# UnsungHeroes.net
KiCad netlist of a schematic drawn in EasyEDA Pro
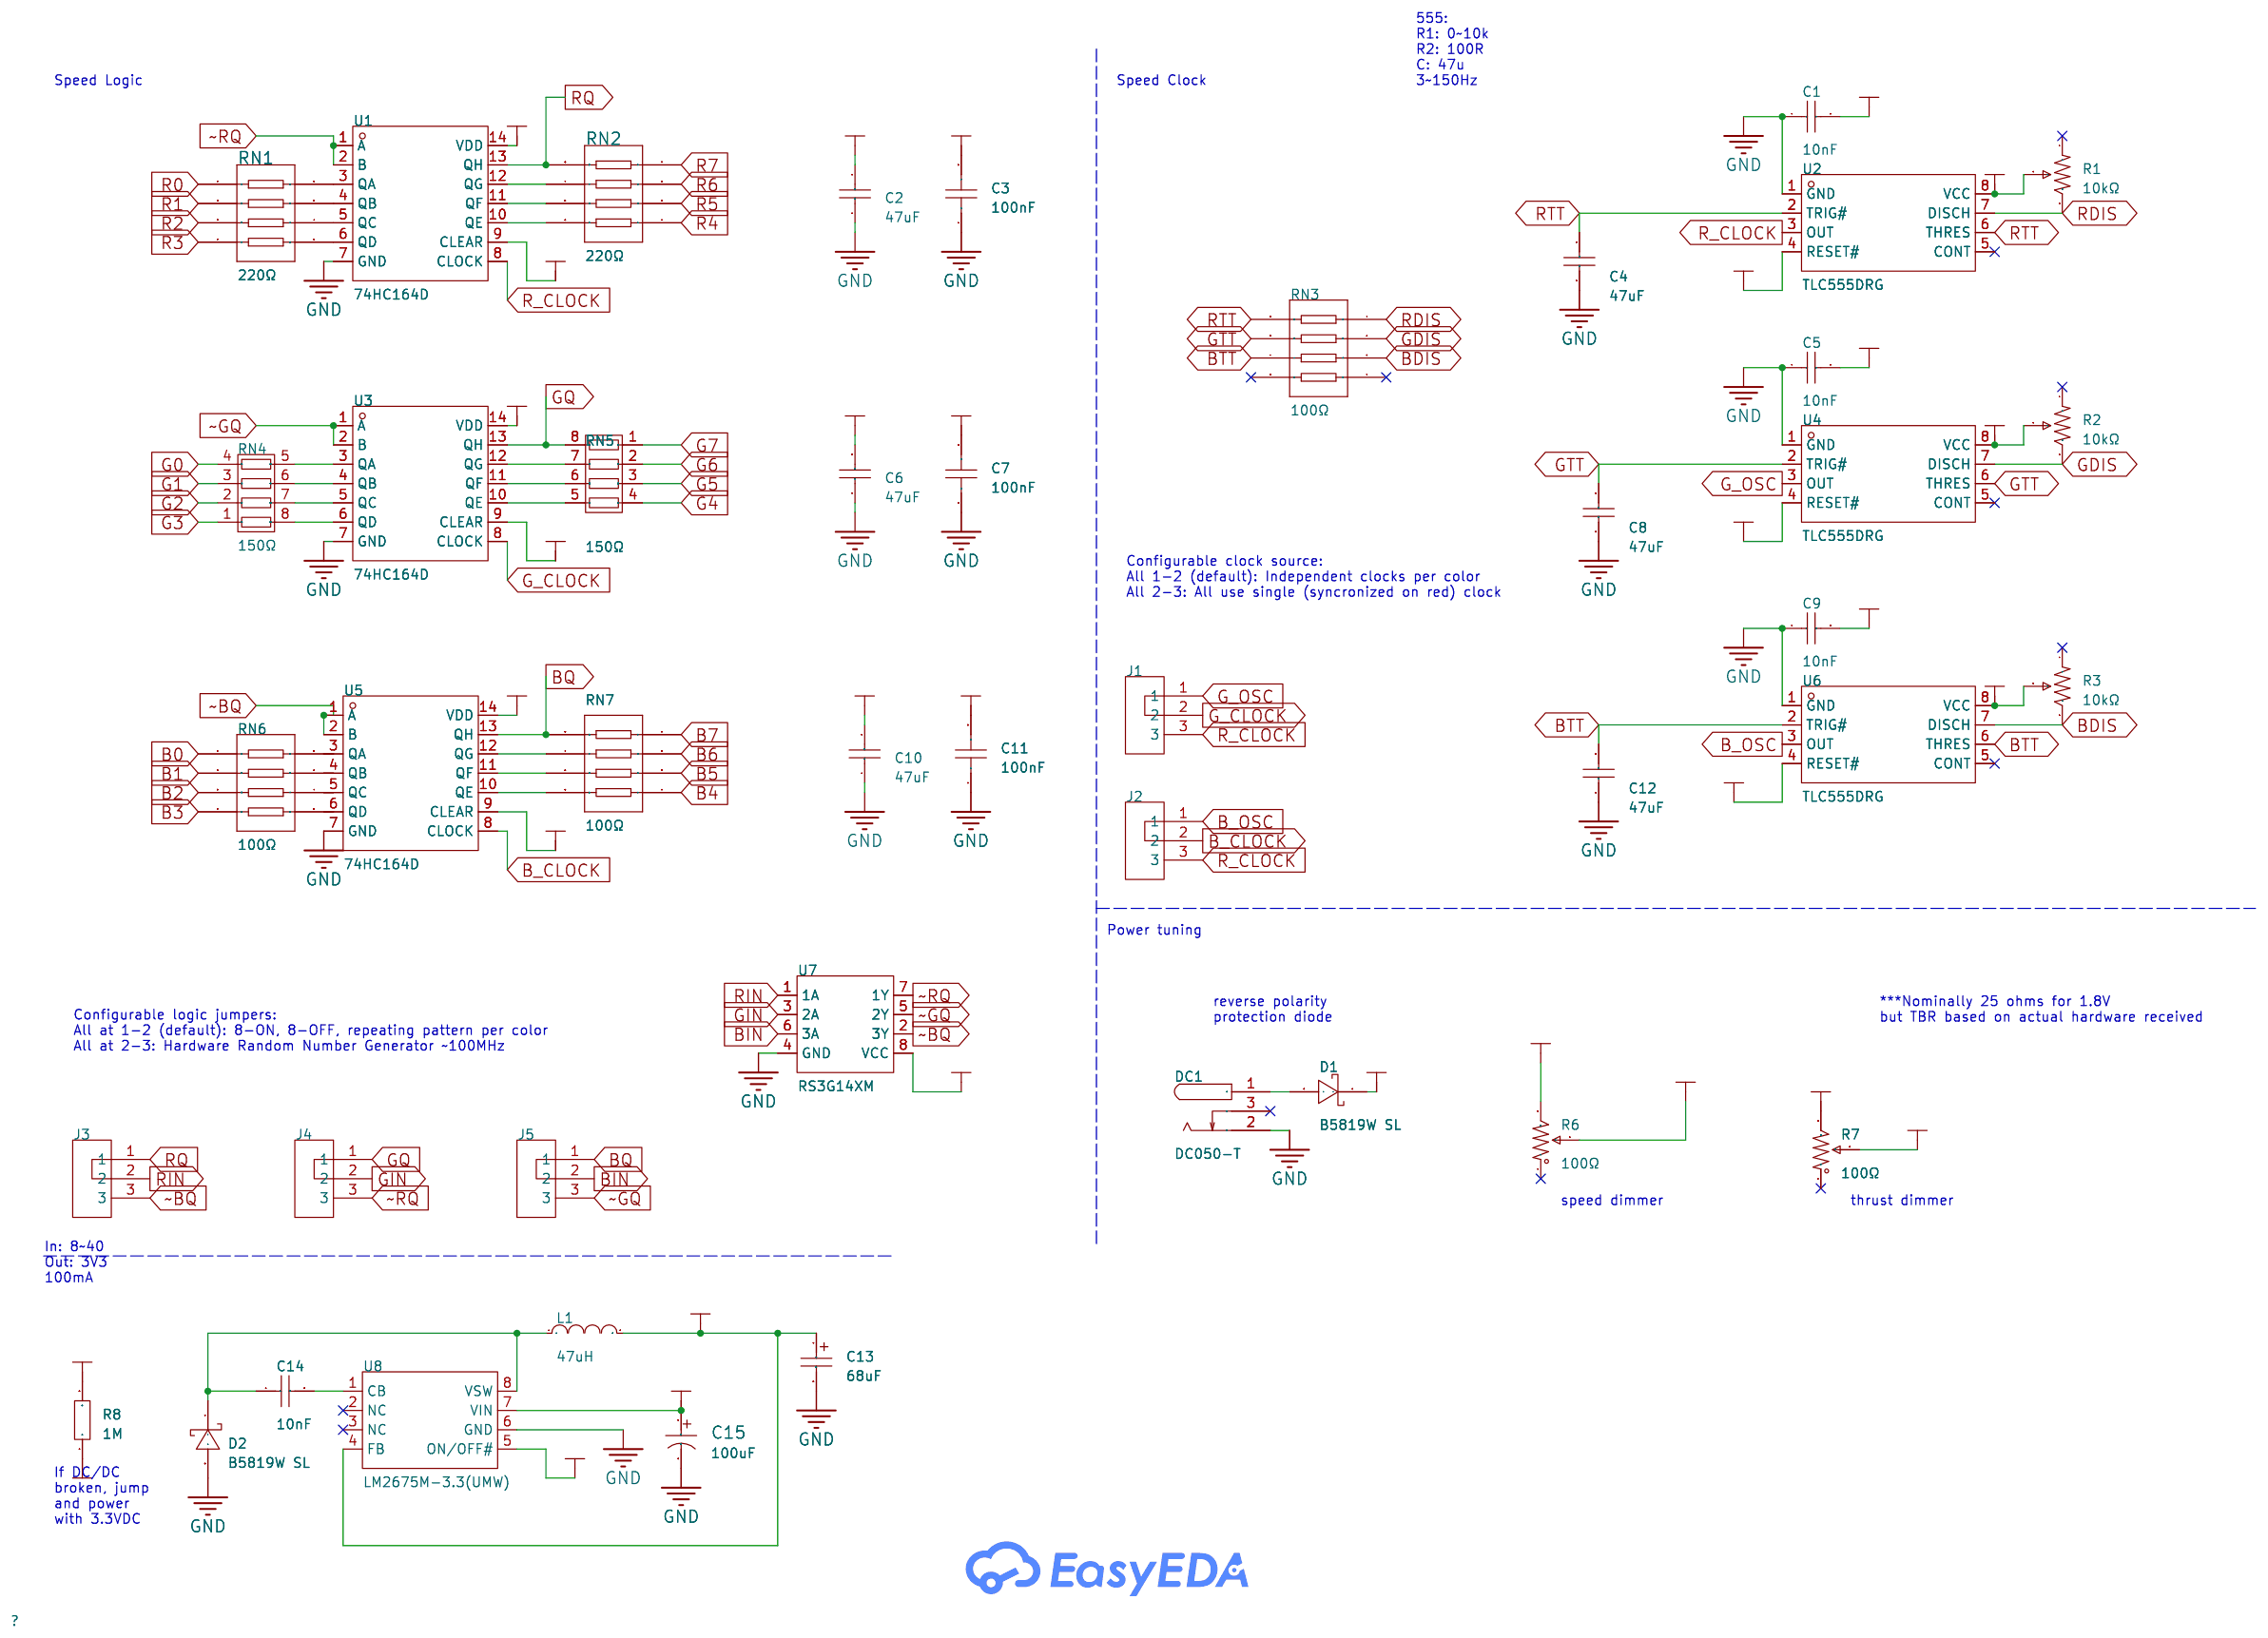
[diagram p0: power_logic]
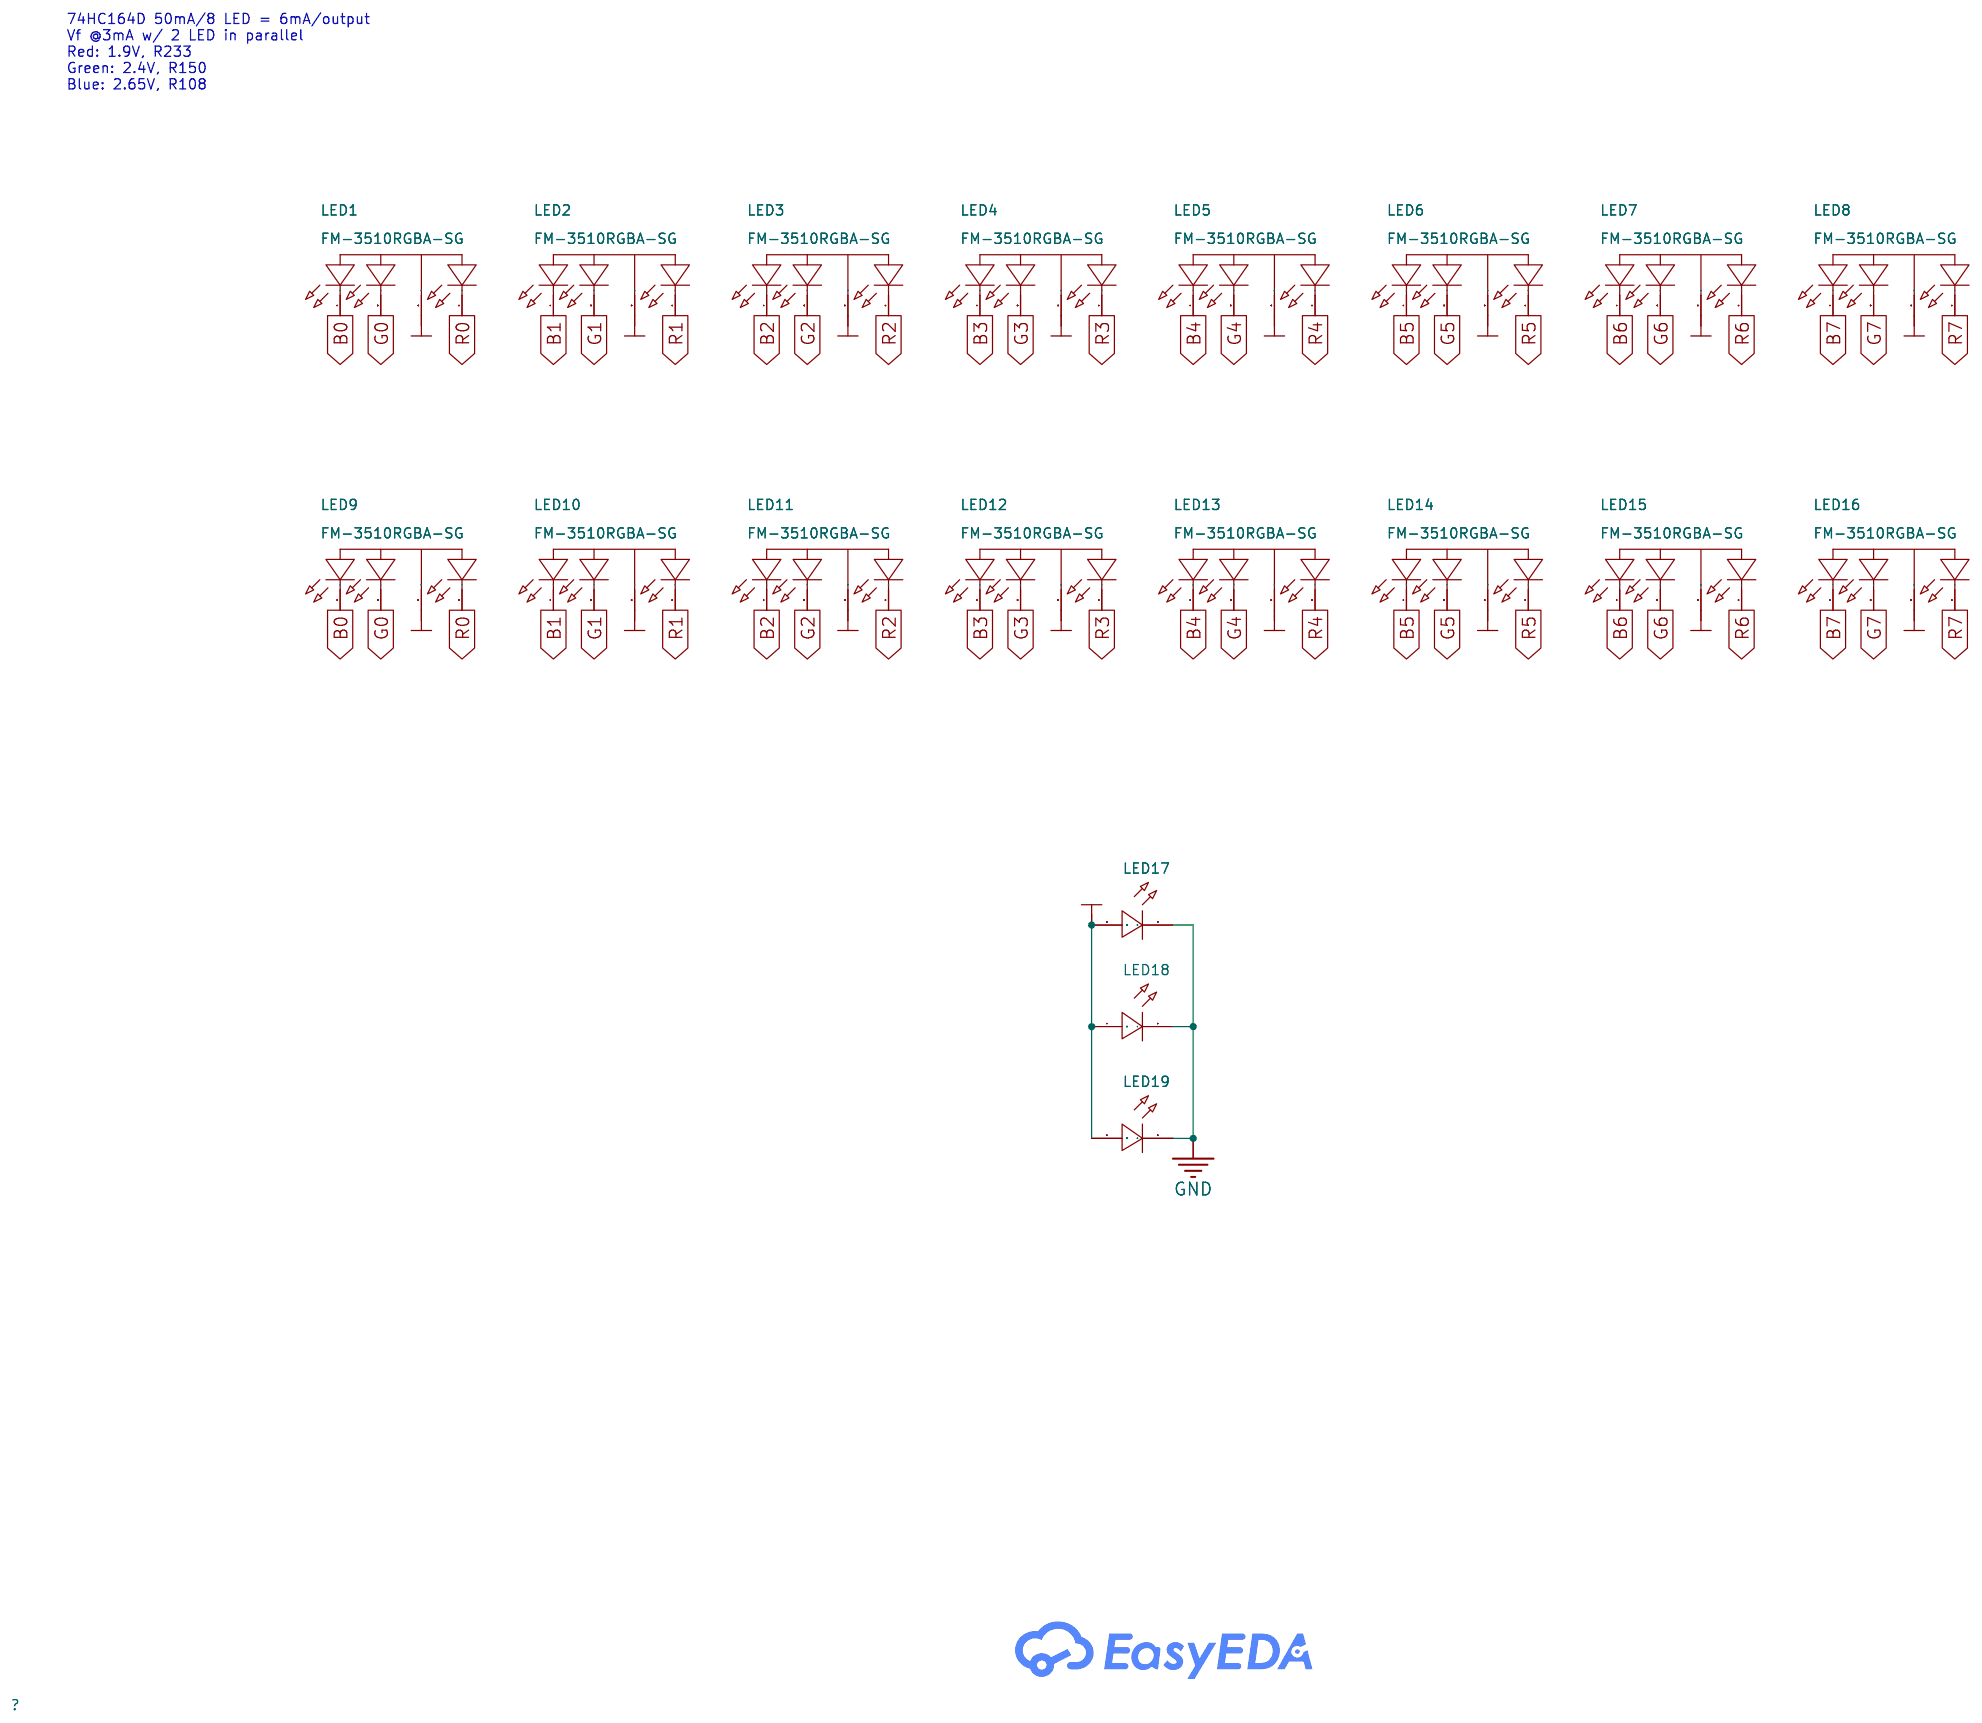
[diagram p1: led]

(export (version "E")
  (design (tool "Eeschema 10.0.6"))
  (components
    (comp (ref "C1")
      (value "10nF")
      (footprint "easyedapro:C0402")
      (description "Capacitance:10nF Tolerance:±10% Tolerance:±10% Voltage Rating:50V Temperature Coefficient:X7R")
      (fields
        (field (name "Manufacturer Part") "CL05B103KB5NNNC")
        (field (name "Manufacturer") "SAMSUNG(三星)")
      )
      (libsource (lib "easyedapro") (part "CL05B103KB5NNNC"))
    )
    (comp (ref "C2")
      (value "47uF")
      (footprint "easyedapro:C0805")
      (description "Capacitance:47uF Tolerance:±20% Tolerance:±20% Voltage Rating:6.3V Temperature Coefficient:X5R")
      (fields
        (field (name "Manufacturer Part") "CL21A476MQYNNNE")
        (field (name "Manufacturer") "SAMSUNG(三星)")
      )
      (libsource (lib "easyedapro") (part "CL21A476MQYNNNE"))
    )
    (comp (ref "C3")
      (value "100nF")
      (footprint "easyedapro:C0402")
      (description "Capacitance:100nF Tolerance:±10% Tolerance:±10% Voltage Rating:16V Temperature Coefficient:X7R")
      (fields
        (field (name "Manufacturer Part") "CL05B104KO5NNNC")
        (field (name "Manufacturer") "SAMSUNG(三星)")
      )
      (libsource (lib "easyedapro") (part "CL05B104KO5NNNC"))
    )
    (comp (ref "C4")
      (value "47uF")
      (footprint "easyedapro:C0805")
      (description "Capacitance:47uF Tolerance:±20% Tolerance:±20% Voltage Rating:6.3V Temperature Coefficient:X5R")
      (fields
        (field (name "Manufacturer Part") "CL21A476MQYNNNE")
        (field (name "Manufacturer") "SAMSUNG(三星)")
      )
      (libsource (lib "easyedapro") (part "CL21A476MQYNNNE"))
    )
    (comp (ref "C5")
      (value "10nF")
      (footprint "easyedapro:C0402")
      (description "Capacitance:10nF Tolerance:±10% Tolerance:±10% Voltage Rating:50V Temperature Coefficient:X7R")
      (fields
        (field (name "Manufacturer Part") "CL05B103KB5NNNC")
        (field (name "Manufacturer") "SAMSUNG(三星)")
      )
      (libsource (lib "easyedapro") (part "CL05B103KB5NNNC"))
    )
    (comp (ref "C6")
      (value "47uF")
      (footprint "easyedapro:C0805")
      (description "Capacitance:47uF Tolerance:±20% Tolerance:±20% Voltage Rating:6.3V Temperature Coefficient:X5R")
      (fields
        (field (name "Manufacturer Part") "CL21A476MQYNNNE")
        (field (name "Manufacturer") "SAMSUNG(三星)")
      )
      (libsource (lib "easyedapro") (part "CL21A476MQYNNNE"))
    )
    (comp (ref "C7")
      (value "100nF")
      (footprint "easyedapro:C0402")
      (description "Capacitance:100nF Tolerance:±10% Tolerance:±10% Voltage Rating:16V Temperature Coefficient:X7R")
      (fields
        (field (name "Manufacturer Part") "CL05B104KO5NNNC")
        (field (name "Manufacturer") "SAMSUNG(三星)")
      )
      (libsource (lib "easyedapro") (part "CL05B104KO5NNNC"))
    )
    (comp (ref "C8")
      (value "47uF")
      (footprint "easyedapro:C0805")
      (description "Capacitance:47uF Tolerance:±20% Tolerance:±20% Voltage Rating:6.3V Temperature Coefficient:X5R")
      (fields
        (field (name "Manufacturer Part") "CL21A476MQYNNNE")
        (field (name "Manufacturer") "SAMSUNG(三星)")
      )
      (libsource (lib "easyedapro") (part "CL21A476MQYNNNE"))
    )
    (comp (ref "C9")
      (value "10nF")
      (footprint "easyedapro:C0402")
      (description "Capacitance:10nF Tolerance:±10% Tolerance:±10% Voltage Rating:50V Temperature Coefficient:X7R")
      (fields
        (field (name "Manufacturer Part") "CL05B103KB5NNNC")
        (field (name "Manufacturer") "SAMSUNG(三星)")
      )
      (libsource (lib "easyedapro") (part "CL05B103KB5NNNC"))
    )
    (comp (ref "C10")
      (value "47uF")
      (footprint "easyedapro:C0805")
      (description "Capacitance:47uF Tolerance:±20% Tolerance:±20% Voltage Rating:6.3V Temperature Coefficient:X5R")
      (fields
        (field (name "Manufacturer Part") "CL21A476MQYNNNE")
        (field (name "Manufacturer") "SAMSUNG(三星)")
      )
      (libsource (lib "easyedapro") (part "CL21A476MQYNNNE"))
    )
    (comp (ref "C11")
      (value "100nF")
      (footprint "easyedapro:C0402")
      (description "Capacitance:100nF Tolerance:±10% Tolerance:±10% Voltage Rating:16V Temperature Coefficient:X7R")
      (fields
        (field (name "Manufacturer Part") "CL05B104KO5NNNC")
        (field (name "Manufacturer") "SAMSUNG(三星)")
      )
      (libsource (lib "easyedapro") (part "CL05B104KO5NNNC"))
    )
    (comp (ref "C12")
      (value "47uF")
      (footprint "easyedapro:C0805")
      (description "Capacitance:47uF Tolerance:±20% Tolerance:±20% Voltage Rating:6.3V Temperature Coefficient:X5R")
      (fields
        (field (name "Manufacturer Part") "CL21A476MQYNNNE")
        (field (name "Manufacturer") "SAMSUNG(三星)")
      )
      (libsource (lib "easyedapro") (part "CL21A476MQYNNNE"))
    )
    (comp (ref "C13")
      (value "68uF")
      (footprint "easyedapro:CAP-SMD_L6.0-W3.2-R-RD")
      (fields (field (name "Manufacturer Part") "TAJC686K016RNJ") (field (name "Manufacturer") "Kyocera AVX"))
      (libsource (lib "easyedapro") (part "TAJC686K016RNJ"))
    )
    (comp (ref "C14")
      (value "10nF")
      (footprint "easyedapro:C0402")
      (description "Capacitance:10nF Tolerance:±10% Tolerance:±10% Voltage Rating:50V Temperature Coefficient:X7R")
      (fields
        (field (name "Manufacturer Part") "CL05B103KB5NNNC")
        (field (name "Manufacturer") "SAMSUNG(三星)")
      )
      (libsource (lib "easyedapro") (part "CL05B103KB5NNNC"))
    )
    (comp (ref "C15")
      (value "100uF")
      (footprint "easyedapro:CAP-SMD_BD8.0-L8.3-W8.3-FD")
      (fields
        (field (name "Manufacturer Part") "UUD1H101MNL1GS")
        (field (name "Manufacturer") "Nichicon(尼吉康)")
      )
      (libsource (lib "easyedapro") (part "UUD1H101MNL1GS"))
    )
    (comp (ref "D1")
      (value "B5819W SL")
      (footprint "easyedapro:SOD-123_L2.7-W1.6-LS3.7-RD-1")
      (fields (field (name "Manufacturer") "CJ(江苏长电/长晶)"))
      (libsource (lib "easyedapro") (part "B5819W_C8598"))
    )
    (comp (ref "D2")
      (value "B5819W SL")
      (footprint "easyedapro:SOD-123_L2.7-W1.6-LS3.7-RD-1")
      (fields (field (name "Manufacturer") "CJ(江苏长电/长晶)"))
      (libsource (lib "easyedapro") (part "B5819W_C8598"))
    )
    (comp (ref "DC1")
      (value "DC050-T")
      (fields (field (name "Manufacturer") "SHOU HAN(首韩)"))
      (libsource (lib "easyedapro") (part "DC050-T"))
    )
    (comp (ref "J1") (value "~") (libsource (lib "easyedapro") (part "jumper3_12")))
    (comp (ref "J2") (value "~") (libsource (lib "easyedapro") (part "jumper3_12")))
    (comp (ref "J3") (value "~") (libsource (lib "easyedapro") (part "jumper3_12")))
    (comp (ref "J4") (value "~") (libsource (lib "easyedapro") (part "jumper3_12")))
    (comp (ref "J5") (value "~") (libsource (lib "easyedapro") (part "jumper3_12")))
    (comp (ref "L1")
      (value "47uH")
      (footprint "easyedapro:L0805")
      (fields (field (name "Manufacturer Part") "CMI201212J470KT") (field (name "Manufacturer") "FH(风华)"))
      (libsource (lib "easyedapro") (part "CMI201212J470KT"))
    )
    (comp (ref "R1")
      (value "10kΩ")
      (footprint "easyedapro:RES-ADJ-SMD_3P-L3.0-W3.8-P1.75-BR")
      (fields (field (name "Manufacturer Part") "TC33X-2-103E") (field (name "Manufacturer") "BOURNS"))
      (libsource (lib "easyedapro") (part "TC33X-2-103E"))
    )
    (comp (ref "R2")
      (value "10kΩ")
      (footprint "easyedapro:RES-ADJ-SMD_3P-L3.0-W3.8-P1.75-BR")
      (fields (field (name "Manufacturer Part") "TC33X-2-103E") (field (name "Manufacturer") "BOURNS"))
      (libsource (lib "easyedapro") (part "TC33X-2-103E"))
    )
    (comp (ref "R3")
      (value "10kΩ")
      (footprint "easyedapro:RES-ADJ-SMD_3P-L3.0-W3.8-P1.75-BR")
      (fields (field (name "Manufacturer Part") "TC33X-2-103E") (field (name "Manufacturer") "BOURNS"))
      (libsource (lib "easyedapro") (part "TC33X-2-103E"))
    )
    (comp (ref "R6")
      (value "100Ω")
      (footprint "easyedapro:RES-ADJ-SMD_TC33X-2-104E")
      (fields (field (name "Manufacturer Part") "TC33X-2-101E") (field (name "Manufacturer") "BOURNS"))
      (libsource (lib "easyedapro") (part "TC33X-2-101E"))
    )
    (comp (ref "R7")
      (value "100Ω")
      (footprint "easyedapro:RES-ADJ-SMD_TC33X-2-104E")
      (fields (field (name "Manufacturer Part") "TC33X-2-101E") (field (name "Manufacturer") "BOURNS"))
      (libsource (lib "easyedapro") (part "TC33X-2-101E"))
    )
    (comp (ref "R8") (value "1M") (footprint "easyedapro:R0805") (libsource (lib "easyedapro") (part "Res")))
    (comp (ref "RN1")
      (value "220Ω")
      (footprint "easyedapro:RES-ARRAY-SMD_0402-8P-L2.0-W1.0-BL")
      (fields
        (field (name "Manufacturer Part") "4D02WGJ0221TCE")
        (field (name "Manufacturer") "UNI-ROYAL(厚声)")
      )
      (libsource (lib "easyedapro") (part "4D02WGJ0221TCE"))
    )
    (comp (ref "RN2")
      (value "220Ω")
      (footprint "easyedapro:RES-ARRAY-SMD_0402-8P-L2.0-W1.0-BL")
      (fields
        (field (name "Manufacturer Part") "4D02WGJ0221TCE")
        (field (name "Manufacturer") "UNI-ROYAL(厚声)")
      )
      (libsource (lib "easyedapro") (part "4D02WGJ0221TCE"))
    )
    (comp (ref "RN3")
      (value "100Ω")
      (footprint "easyedapro:RES-ARRAY-SMD_0402-8P-L2.0-W1.0-BL")
      (fields
        (field (name "Manufacturer Part") "4D02WGJ0101TCE")
        (field (name "Manufacturer") "UNI-ROYAL(厚声)")
      )
      (libsource (lib "easyedapro") (part "4D02WGJ0101TCE"))
    )
    (comp (ref "RN4")
      (value "150Ω")
      (footprint "easyedapro:RES-ARRAY-SMD_0402-8P-L2.0-W1.0-BL")
      (fields (field (name "Manufacturer Part") "RTA02-4D151JTH") (field (name "Manufacturer") "RALEC(旺诠)"))
      (libsource (lib "easyedapro") (part "RTA02-4D151JTH"))
    )
    (comp (ref "RN5")
      (value "150Ω")
      (footprint "easyedapro:RES-ARRAY-SMD_0402-8P-L2.0-W1.0-BL")
      (fields (field (name "Manufacturer Part") "RTA02-4D151JTH") (field (name "Manufacturer") "RALEC(旺诠)"))
      (libsource (lib "easyedapro") (part "RTA02-4D151JTH"))
    )
    (comp (ref "RN6")
      (value "100Ω")
      (footprint "easyedapro:RES-ARRAY-SMD_0402-8P-L2.0-W1.0-BL")
      (fields
        (field (name "Manufacturer Part") "4D02WGJ0101TCE")
        (field (name "Manufacturer") "UNI-ROYAL(厚声)")
      )
      (libsource (lib "easyedapro") (part "4D02WGJ0101TCE"))
    )
    (comp (ref "RN7")
      (value "100Ω")
      (footprint "easyedapro:RES-ARRAY-SMD_0402-8P-L2.0-W1.0-BL")
      (fields
        (field (name "Manufacturer Part") "4D02WGJ0101TCE")
        (field (name "Manufacturer") "UNI-ROYAL(厚声)")
      )
      (libsource (lib "easyedapro") (part "4D02WGJ0101TCE"))
    )
    (comp (ref "U1")
      (value "74HC164D")
      (footprint "easyedapro:SOP-14_L8.6-W3.9-P1.27-LS6.0-BL")
      (fields (field (name "Manufacturer") "FM(富满)"))
      (libsource (lib "easyedapro") (part "74HC164D"))
    )
    (comp (ref "U2")
      (value "TLC555DRG")
      (fields (field (name "Manufacturer") "HGC(深圳汉芯)"))
      (libsource (lib "easyedapro") (part "TLC555DRG"))
    )
    (comp (ref "U3")
      (value "74HC164D")
      (footprint "easyedapro:SOP-14_L8.6-W3.9-P1.27-LS6.0-BL")
      (fields (field (name "Manufacturer") "FM(富满)"))
      (libsource (lib "easyedapro") (part "74HC164D"))
    )
    (comp (ref "U4")
      (value "TLC555DRG")
      (fields (field (name "Manufacturer") "HGC(深圳汉芯)"))
      (libsource (lib "easyedapro") (part "TLC555DRG"))
    )
    (comp (ref "U5")
      (value "74HC164D")
      (footprint "easyedapro:SOP-14_L8.6-W3.9-P1.27-LS6.0-BL")
      (fields (field (name "Manufacturer") "FM(富满)"))
      (libsource (lib "easyedapro") (part "74HC164D"))
    )
    (comp (ref "U6")
      (value "TLC555DRG")
      (fields (field (name "Manufacturer") "HGC(深圳汉芯)"))
      (libsource (lib "easyedapro") (part "TLC555DRG"))
    )
    (comp (ref "U7")
      (value "RS3G14XM")
      (footprint "easyedapro:MSOP-8_L3.0-W3.0-P0.65-LS4.9-BL")
      (fields (field (name "Manufacturer") "RUNIC(润石)"))
      (libsource (lib "easyedapro") (part "RS3G14XM"))
    )
    (comp (ref "U8")
      (value "LM2675M-3.3(UMW)")
      (footprint "easyedapro:SOIC-8_L4.9-W3.8-P1.27-LS6.0-BL")
      (fields (field (name "Manufacturer") "UMW(友台半导体)"))
      (libsource (lib "easyedapro") (part "LM2675M-3.3_C5563863"))
    )
    (comp (ref "LED1")
      (value "FM-3510RGBA-SG")
      (footprint "easyedapro:LED-SMD_FM-3510RGBA-SG")
      (fields (field (name "Manufacturer") "国星光电"))
      (libsource (lib "easyedapro") (part "FM-3510RGBA-SG"))
    )
    (comp (ref "LED2")
      (value "FM-3510RGBA-SG")
      (footprint "easyedapro:LED-SMD_FM-3510RGBA-SG")
      (fields (field (name "Manufacturer") "国星光电"))
      (libsource (lib "easyedapro") (part "FM-3510RGBA-SG"))
    )
    (comp (ref "LED3")
      (value "FM-3510RGBA-SG")
      (footprint "easyedapro:LED-SMD_FM-3510RGBA-SG")
      (fields (field (name "Manufacturer") "国星光电"))
      (libsource (lib "easyedapro") (part "FM-3510RGBA-SG"))
    )
    (comp (ref "LED4")
      (value "FM-3510RGBA-SG")
      (footprint "easyedapro:LED-SMD_FM-3510RGBA-SG")
      (fields (field (name "Manufacturer") "国星光电"))
      (libsource (lib "easyedapro") (part "FM-3510RGBA-SG"))
    )
    (comp (ref "LED5")
      (value "FM-3510RGBA-SG")
      (footprint "easyedapro:LED-SMD_FM-3510RGBA-SG")
      (fields (field (name "Manufacturer") "国星光电"))
      (libsource (lib "easyedapro") (part "FM-3510RGBA-SG"))
    )
    (comp (ref "LED6")
      (value "FM-3510RGBA-SG")
      (footprint "easyedapro:LED-SMD_FM-3510RGBA-SG")
      (fields (field (name "Manufacturer") "国星光电"))
      (libsource (lib "easyedapro") (part "FM-3510RGBA-SG"))
    )
    (comp (ref "LED7")
      (value "FM-3510RGBA-SG")
      (footprint "easyedapro:LED-SMD_FM-3510RGBA-SG")
      (fields (field (name "Manufacturer") "国星光电"))
      (libsource (lib "easyedapro") (part "FM-3510RGBA-SG"))
    )
    (comp (ref "LED8")
      (value "FM-3510RGBA-SG")
      (footprint "easyedapro:LED-SMD_FM-3510RGBA-SG")
      (fields (field (name "Manufacturer") "国星光电"))
      (libsource (lib "easyedapro") (part "FM-3510RGBA-SG"))
    )
    (comp (ref "LED9")
      (value "FM-3510RGBA-SG")
      (footprint "easyedapro:LED-SMD_FM-3510RGBA-SG")
      (fields (field (name "Manufacturer") "国星光电"))
      (libsource (lib "easyedapro") (part "FM-3510RGBA-SG"))
    )
    (comp (ref "LED10")
      (value "FM-3510RGBA-SG")
      (footprint "easyedapro:LED-SMD_FM-3510RGBA-SG")
      (fields (field (name "Manufacturer") "国星光电"))
      (libsource (lib "easyedapro") (part "FM-3510RGBA-SG"))
    )
    (comp (ref "LED11")
      (value "FM-3510RGBA-SG")
      (footprint "easyedapro:LED-SMD_FM-3510RGBA-SG")
      (fields (field (name "Manufacturer") "国星光电"))
      (libsource (lib "easyedapro") (part "FM-3510RGBA-SG"))
    )
    (comp (ref "LED12")
      (value "FM-3510RGBA-SG")
      (footprint "easyedapro:LED-SMD_FM-3510RGBA-SG")
      (fields (field (name "Manufacturer") "国星光电"))
      (libsource (lib "easyedapro") (part "FM-3510RGBA-SG"))
    )
    (comp (ref "LED13")
      (value "FM-3510RGBA-SG")
      (footprint "easyedapro:LED-SMD_FM-3510RGBA-SG")
      (fields (field (name "Manufacturer") "国星光电"))
      (libsource (lib "easyedapro") (part "FM-3510RGBA-SG"))
    )
    (comp (ref "LED14")
      (value "FM-3510RGBA-SG")
      (footprint "easyedapro:LED-SMD_FM-3510RGBA-SG")
      (fields (field (name "Manufacturer") "国星光电"))
      (libsource (lib "easyedapro") (part "FM-3510RGBA-SG"))
    )
    (comp (ref "LED15")
      (value "FM-3510RGBA-SG")
      (footprint "easyedapro:LED-SMD_FM-3510RGBA-SG")
      (fields (field (name "Manufacturer") "国星光电"))
      (libsource (lib "easyedapro") (part "FM-3510RGBA-SG"))
    )
    (comp (ref "LED16")
      (value "FM-3510RGBA-SG")
      (footprint "easyedapro:LED-SMD_FM-3510RGBA-SG")
      (fields (field (name "Manufacturer") "国星光电"))
      (libsource (lib "easyedapro") (part "FM-3510RGBA-SG"))
    )
    (comp (ref "LED17")
      (value "~")
      (footprint "easyedapro:LED-TH_BD3.0-P2.54-FD")
      (libsource (lib "easyedapro") (part "LED_TH-R"))
    )
    (comp (ref "LED18")
      (value "~")
      (footprint "easyedapro:LED-TH_BD3.0-P2.54-FD")
      (libsource (lib "easyedapro") (part "LED_TH-R"))
    )
    (comp (ref "LED19")
      (value "~")
      (footprint "easyedapro:LED-TH_BD3.0-P2.54-FD")
      (libsource (lib "easyedapro") (part "LED_TH-R"))
    )
  )
  (nets
    (net (code "1") (name "3V3") (class "Default")
      (node (ref "C13") (pin "1") (pinfunction "1_1") (pintype "input"))
      (node (ref "L1") (pin "2") (pinfunction "2_2") (pintype "unspecified"))
      (node (ref "R6") (pin "3") (pinfunction "3_3") (pintype "unspecified"))
      (node (ref "R7") (pin "3") (pinfunction "3_3") (pintype "unspecified"))
      (node (ref "R8") (pin "1") (pinfunction "1_1") (pintype "input"))
      (node (ref "U8") (pin "4") (pinfunction "FB_4") (pintype "unspecified"))
    )
    (net (code "2") (name "3V3S") (class "Default")
      (node (ref "C1") (pin "2") (pinfunction "2_2") (pintype "input"))
      (node (ref "C10") (pin "2") (pinfunction "2_2") (pintype "input"))
      (node (ref "C11") (pin "2") (pinfunction "2_2") (pintype "unspecified"))
      (node (ref "C2") (pin "2") (pinfunction "2_2") (pintype "input"))
      (node (ref "C3") (pin "2") (pinfunction "2_2") (pintype "unspecified"))
      (node (ref "C5") (pin "2") (pinfunction "2_2") (pintype "input"))
      (node (ref "C6") (pin "2") (pinfunction "2_2") (pintype "input"))
      (node (ref "C7") (pin "2") (pinfunction "2_2") (pintype "unspecified"))
      (node (ref "C9") (pin "2") (pinfunction "2_2") (pintype "input"))
      (node (ref "LED1") (pin "2") (pinfunction "+_2") (pintype "unspecified"))
      (node (ref "LED10") (pin "2") (pinfunction "+_2") (pintype "unspecified"))
      (node (ref "LED11") (pin "2") (pinfunction "+_2") (pintype "unspecified"))
      (node (ref "LED12") (pin "2") (pinfunction "+_2") (pintype "unspecified"))
      (node (ref "LED13") (pin "2") (pinfunction "+_2") (pintype "unspecified"))
      (node (ref "LED14") (pin "2") (pinfunction "+_2") (pintype "unspecified"))
      (node (ref "LED15") (pin "2") (pinfunction "+_2") (pintype "unspecified"))
      (node (ref "LED16") (pin "2") (pinfunction "+_2") (pintype "unspecified"))
      (node (ref "LED2") (pin "2") (pinfunction "+_2") (pintype "unspecified"))
      (node (ref "LED3") (pin "2") (pinfunction "+_2") (pintype "unspecified"))
      (node (ref "LED4") (pin "2") (pinfunction "+_2") (pintype "unspecified"))
      (node (ref "LED5") (pin "2") (pinfunction "+_2") (pintype "unspecified"))
      (node (ref "LED6") (pin "2") (pinfunction "+_2") (pintype "unspecified"))
      (node (ref "LED7") (pin "2") (pinfunction "+_2") (pintype "unspecified"))
      (node (ref "LED8") (pin "2") (pinfunction "+_2") (pintype "unspecified"))
      (node (ref "LED9") (pin "2") (pinfunction "+_2") (pintype "unspecified"))
      (node (ref "R1") (pin "2") (pinfunction "2_2") (pintype "unspecified"))
      (node (ref "R2") (pin "2") (pinfunction "2_2") (pintype "unspecified"))
      (node (ref "R3") (pin "2") (pinfunction "2_2") (pintype "unspecified"))
      (node (ref "R6") (pin "2") (pinfunction "2_2") (pintype "unspecified"))
      (node (ref "U1") (pin "14") (pinfunction "VDD_14") (pintype "unspecified"))
      (node (ref "U1") (pin "9") (pinfunction "CLEAR_9") (pintype "unspecified"))
      (node (ref "U2") (pin "4") (pinfunction "RESET#_4") (pintype "unspecified"))
      (node (ref "U2") (pin "8") (pinfunction "VCC_8") (pintype "unspecified"))
      (node (ref "U3") (pin "14") (pinfunction "VDD_14") (pintype "unspecified"))
      (node (ref "U3") (pin "9") (pinfunction "CLEAR_9") (pintype "unspecified"))
      (node (ref "U4") (pin "4") (pinfunction "RESET#_4") (pintype "unspecified"))
      (node (ref "U4") (pin "8") (pinfunction "VCC_8") (pintype "unspecified"))
      (node (ref "U5") (pin "14") (pinfunction "VDD_14") (pintype "unspecified"))
      (node (ref "U5") (pin "9") (pinfunction "CLEAR_9") (pintype "unspecified"))
      (node (ref "U6") (pin "4") (pinfunction "RESET#_4") (pintype "unspecified"))
      (node (ref "U6") (pin "8") (pinfunction "VCC_8") (pintype "unspecified"))
      (node (ref "U7") (pin "8") (pinfunction "VCC_8") (pintype "unspecified"))
    )
    (net (code "3") (name "3V3T") (class "Default")
      (node (ref "LED17") (pin "1") (pinfunction "C_1") (pintype "input"))
      (node (ref "LED18") (pin "1") (pinfunction "C_1") (pintype "input"))
      (node (ref "LED19") (pin "1") (pinfunction "C_1") (pintype "input"))
      (node (ref "R7") (pin "2") (pinfunction "2_2") (pintype "unspecified"))
    )
    (net (code "4") (name "24V") (class "Default")
      (node (ref "C15") (pin "1") (pinfunction "1_1") (pintype "input"))
      (node (ref "D1") (pin "1") (pinfunction "-_1") (pintype "unspecified"))
      (node (ref "R8") (pin "2") (pinfunction "2_2") (pintype "input"))
      (node (ref "U8") (pin "5") (pinfunction "ON/OFF#_5") (pintype "unspecified"))
      (node (ref "U8") (pin "7") (pinfunction "VIN_7") (pintype "unspecified"))
    )
    (net (code "5") (name "B0") (class "Default")
      (node (ref "LED1") (pin "4") (pinfunction "-_4") (pintype "unspecified"))
      (node (ref "LED9") (pin "4") (pinfunction "-_4") (pintype "unspecified"))
      (node (ref "RN6") (pin "4") (pinfunction "4_4") (pintype "input"))
    )
    (net (code "6") (name "B1") (class "Default")
      (node (ref "LED10") (pin "4") (pinfunction "-_4") (pintype "unspecified"))
      (node (ref "LED2") (pin "4") (pinfunction "-_4") (pintype "unspecified"))
      (node (ref "RN6") (pin "3") (pinfunction "3_3") (pintype "input"))
    )
    (net (code "7") (name "B2") (class "Default")
      (node (ref "LED11") (pin "4") (pinfunction "-_4") (pintype "unspecified"))
      (node (ref "LED3") (pin "4") (pinfunction "-_4") (pintype "unspecified"))
      (node (ref "RN6") (pin "2") (pinfunction "2_2") (pintype "input"))
    )
    (net (code "8") (name "B3") (class "Default")
      (node (ref "LED12") (pin "4") (pinfunction "-_4") (pintype "unspecified"))
      (node (ref "LED4") (pin "4") (pinfunction "-_4") (pintype "unspecified"))
      (node (ref "RN6") (pin "1") (pinfunction "1_1") (pintype "input"))
    )
    (net (code "9") (name "B4") (class "Default")
      (node (ref "LED13") (pin "4") (pinfunction "-_4") (pintype "unspecified"))
      (node (ref "LED5") (pin "4") (pinfunction "-_4") (pintype "unspecified"))
      (node (ref "RN7") (pin "4") (pinfunction "4_4") (pintype "input"))
    )
    (net (code "10") (name "B5") (class "Default")
      (node (ref "LED14") (pin "4") (pinfunction "-_4") (pintype "unspecified"))
      (node (ref "LED6") (pin "4") (pinfunction "-_4") (pintype "unspecified"))
      (node (ref "RN7") (pin "3") (pinfunction "3_3") (pintype "input"))
    )
    (net (code "11") (name "B6") (class "Default")
      (node (ref "LED15") (pin "4") (pinfunction "-_4") (pintype "unspecified"))
      (node (ref "LED7") (pin "4") (pinfunction "-_4") (pintype "unspecified"))
      (node (ref "RN7") (pin "2") (pinfunction "2_2") (pintype "input"))
    )
    (net (code "12") (name "B7") (class "Default")
      (node (ref "LED16") (pin "4") (pinfunction "-_4") (pintype "unspecified"))
      (node (ref "LED8") (pin "4") (pinfunction "-_4") (pintype "unspecified"))
      (node (ref "RN7") (pin "1") (pinfunction "1_1") (pintype "input"))
    )
    (net (code "13") (name "BDIS") (class "Default")
      (node (ref "R3") (pin "3") (pinfunction "3_3") (pintype "unspecified"))
      (node (ref "RN3") (pin "2") (pinfunction "2_2") (pintype "input"))
      (node (ref "U6") (pin "7") (pinfunction "DISCH_7") (pintype "unspecified"))
    )
    (net (code "14") (name "BIN") (class "Default")
      (node (ref "J5") (pin "2") (pinfunction "2_2") (pintype "input"))
      (node (ref "U7") (pin "6") (pinfunction "3A_6") (pintype "unspecified"))
    )
    (net (code "15") (name "BQ") (class "Default")
      (node (ref "J5") (pin "1") (pinfunction "1_1") (pintype "input"))
      (node (ref "RN7") (pin "8") (pinfunction "8_8") (pintype "input"))
      (node (ref "U5") (pin "13") (pinfunction "QH_13") (pintype "unspecified"))
    )
    (net (code "16") (name "BTT") (class "Default")
      (node (ref "C12") (pin "1") (pinfunction "1_1") (pintype "input"))
      (node (ref "RN3") (pin "7") (pinfunction "7_7") (pintype "input"))
      (node (ref "U6") (pin "2") (pinfunction "TRIG#_2") (pintype "unspecified"))
      (node (ref "U6") (pin "6") (pinfunction "THRES_6") (pintype "unspecified"))
    )
    (net (code "17") (name "B_CLOCK") (class "Default")
      (node (ref "J2") (pin "2") (pinfunction "2_2") (pintype "input"))
      (node (ref "U5") (pin "8") (pinfunction "CLOCK_8") (pintype "unspecified"))
    )
    (net (code "18") (name "B_OSC") (class "Default")
      (node (ref "J2") (pin "1") (pinfunction "1_1") (pintype "input"))
      (node (ref "U6") (pin "3") (pinfunction "OUT_3") (pintype "unspecified"))
    )
    (net (code "19") (name "G0") (class "Default")
      (node (ref "LED1") (pin "3") (pinfunction "-_3") (pintype "unspecified"))
      (node (ref "LED9") (pin "3") (pinfunction "-_3") (pintype "unspecified"))
      (node (ref "RN4") (pin "4") (pinfunction "R4.1_4") (pintype "unspecified"))
    )
    (net (code "20") (name "G1") (class "Default")
      (node (ref "LED10") (pin "3") (pinfunction "-_3") (pintype "unspecified"))
      (node (ref "LED2") (pin "3") (pinfunction "-_3") (pintype "unspecified"))
      (node (ref "RN4") (pin "3") (pinfunction "R3.1_3") (pintype "unspecified"))
    )
    (net (code "21") (name "G2") (class "Default")
      (node (ref "LED11") (pin "3") (pinfunction "-_3") (pintype "unspecified"))
      (node (ref "LED3") (pin "3") (pinfunction "-_3") (pintype "unspecified"))
      (node (ref "RN4") (pin "2") (pinfunction "R2.1_2") (pintype "unspecified"))
    )
    (net (code "22") (name "G3") (class "Default")
      (node (ref "LED12") (pin "3") (pinfunction "-_3") (pintype "unspecified"))
      (node (ref "LED4") (pin "3") (pinfunction "-_3") (pintype "unspecified"))
      (node (ref "RN4") (pin "1") (pinfunction "R1.1_1") (pintype "unspecified"))
    )
    (net (code "23") (name "G4") (class "Default")
      (node (ref "LED13") (pin "3") (pinfunction "-_3") (pintype "unspecified"))
      (node (ref "LED5") (pin "3") (pinfunction "-_3") (pintype "unspecified"))
      (node (ref "RN5") (pin "4") (pinfunction "R4.1_4") (pintype "unspecified"))
    )
    (net (code "24") (name "G5") (class "Default")
      (node (ref "LED14") (pin "3") (pinfunction "-_3") (pintype "unspecified"))
      (node (ref "LED6") (pin "3") (pinfunction "-_3") (pintype "unspecified"))
      (node (ref "RN5") (pin "3") (pinfunction "R3.1_3") (pintype "unspecified"))
    )
    (net (code "25") (name "G6") (class "Default")
      (node (ref "LED15") (pin "3") (pinfunction "-_3") (pintype "unspecified"))
      (node (ref "LED7") (pin "3") (pinfunction "-_3") (pintype "unspecified"))
      (node (ref "RN5") (pin "2") (pinfunction "R2.1_2") (pintype "unspecified"))
    )
    (net (code "26") (name "G7") (class "Default")
      (node (ref "LED16") (pin "3") (pinfunction "-_3") (pintype "unspecified"))
      (node (ref "LED8") (pin "3") (pinfunction "-_3") (pintype "unspecified"))
      (node (ref "RN5") (pin "1") (pinfunction "R1.1_1") (pintype "unspecified"))
    )
    (net (code "27") (name "GDIS") (class "Default")
      (node (ref "R2") (pin "3") (pinfunction "3_3") (pintype "unspecified"))
      (node (ref "RN3") (pin "3") (pinfunction "3_3") (pintype "input"))
      (node (ref "U4") (pin "7") (pinfunction "DISCH_7") (pintype "unspecified"))
    )
    (net (code "28") (name "GIN") (class "Default")
      (node (ref "J4") (pin "2") (pinfunction "2_2") (pintype "input"))
      (node (ref "U7") (pin "3") (pinfunction "2A_3") (pintype "unspecified"))
    )
    (net (code "29") (name "GND") (class "Default")
      (node (ref "C1") (pin "1") (pinfunction "1_1") (pintype "input"))
      (node (ref "C10") (pin "1") (pinfunction "1_1") (pintype "input"))
      (node (ref "C11") (pin "1") (pinfunction "1_1") (pintype "unspecified"))
      (node (ref "C12") (pin "2") (pinfunction "2_2") (pintype "input"))
      (node (ref "C13") (pin "2") (pinfunction "2_2") (pintype "input"))
      (node (ref "C15") (pin "2") (pinfunction "2_2") (pintype "input"))
      (node (ref "C2") (pin "1") (pinfunction "1_1") (pintype "input"))
      (node (ref "C3") (pin "1") (pinfunction "1_1") (pintype "unspecified"))
      (node (ref "C4") (pin "2") (pinfunction "2_2") (pintype "input"))
      (node (ref "C5") (pin "1") (pinfunction "1_1") (pintype "input"))
      (node (ref "C6") (pin "1") (pinfunction "1_1") (pintype "input"))
      (node (ref "C7") (pin "1") (pinfunction "1_1") (pintype "unspecified"))
      (node (ref "C8") (pin "2") (pinfunction "2_2") (pintype "input"))
      (node (ref "C9") (pin "1") (pinfunction "1_1") (pintype "input"))
      (node (ref "D2") (pin "2") (pinfunction "+_2") (pintype "unspecified"))
      (node (ref "DC1") (pin "2") (pinfunction "2_2") (pintype "unspecified"))
      (node (ref "LED17") (pin "2") (pinfunction "A_2") (pintype "input"))
      (node (ref "LED18") (pin "2") (pinfunction "A_2") (pintype "input"))
      (node (ref "LED19") (pin "2") (pinfunction "A_2") (pintype "input"))
      (node (ref "U1") (pin "7") (pinfunction "GND_7") (pintype "unspecified"))
      (node (ref "U2") (pin "1") (pinfunction "GND_1") (pintype "unspecified"))
      (node (ref "U3") (pin "7") (pinfunction "GND_7") (pintype "unspecified"))
      (node (ref "U4") (pin "1") (pinfunction "GND_1") (pintype "unspecified"))
      (node (ref "U5") (pin "7") (pinfunction "GND_7") (pintype "unspecified"))
      (node (ref "U6") (pin "1") (pinfunction "GND_1") (pintype "unspecified"))
      (node (ref "U7") (pin "4") (pinfunction "GND_4") (pintype "unspecified"))
      (node (ref "U8") (pin "6") (pinfunction "GND_6") (pintype "unspecified"))
    )
    (net (code "30") (name "GQ") (class "Default")
      (node (ref "J4") (pin "1") (pinfunction "1_1") (pintype "input"))
      (node (ref "RN5") (pin "8") (pinfunction "R1.2_8") (pintype "unspecified"))
      (node (ref "U3") (pin "13") (pinfunction "QH_13") (pintype "unspecified"))
    )
    (net (code "31") (name "GTT") (class "Default")
      (node (ref "C8") (pin "1") (pinfunction "1_1") (pintype "input"))
      (node (ref "RN3") (pin "6") (pinfunction "6_6") (pintype "input"))
      (node (ref "U4") (pin "2") (pinfunction "TRIG#_2") (pintype "unspecified"))
      (node (ref "U4") (pin "6") (pinfunction "THRES_6") (pintype "unspecified"))
    )
    (net (code "32") (name "G_CLOCK") (class "Default")
      (node (ref "J1") (pin "2") (pinfunction "2_2") (pintype "input"))
      (node (ref "U3") (pin "8") (pinfunction "CLOCK_8") (pintype "unspecified"))
    )
    (net (code "33") (name "G_OSC") (class "Default")
      (node (ref "J1") (pin "1") (pinfunction "1_1") (pintype "input"))
      (node (ref "U4") (pin "3") (pinfunction "OUT_3") (pintype "unspecified"))
    )
    (net (code "34") (name "Net-(D1-+)") (class "Default")
      (node (ref "D1") (pin "2") (pinfunction "+_2") (pintype "unspecified"))
      (node (ref "DC1") (pin "1") (pinfunction "1_1") (pintype "unspecified"))
    )
    (net (code "35") (name "Net-(D2--)") (class "Default")
      (node (ref "C14") (pin "1") (pinfunction "1_1") (pintype "input"))
      (node (ref "D2") (pin "1") (pinfunction "-_1") (pintype "unspecified"))
      (node (ref "L1") (pin "1") (pinfunction "1_1") (pintype "unspecified"))
      (node (ref "U8") (pin "8") (pinfunction "VSW_8") (pintype "unspecified"))
    )
    (net (code "36") (name "Net-(RN4-R1.2)") (class "Default")
      (node (ref "RN4") (pin "8") (pinfunction "R1.2_8") (pintype "unspecified"))
      (node (ref "U3") (pin "6") (pinfunction "QD_6") (pintype "unspecified"))
    )
    (net (code "37") (name "Net-(RN4-R2.2)") (class "Default")
      (node (ref "RN4") (pin "7") (pinfunction "R2.2_7") (pintype "unspecified"))
      (node (ref "U3") (pin "5") (pinfunction "QC_5") (pintype "unspecified"))
    )
    (net (code "38") (name "Net-(RN4-R3.2)") (class "Default")
      (node (ref "RN4") (pin "6") (pinfunction "R3.2_6") (pintype "unspecified"))
      (node (ref "U3") (pin "4") (pinfunction "QB_4") (pintype "unspecified"))
    )
    (net (code "39") (name "Net-(RN4-R4.2)") (class "Default")
      (node (ref "RN4") (pin "5") (pinfunction "R4.2_5") (pintype "unspecified"))
      (node (ref "U3") (pin "3") (pinfunction "QA_3") (pintype "unspecified"))
    )
    (net (code "40") (name "Net-(RN5-R2.2)") (class "Default")
      (node (ref "RN5") (pin "7") (pinfunction "R2.2_7") (pintype "unspecified"))
      (node (ref "U3") (pin "12") (pinfunction "QG_12") (pintype "unspecified"))
    )
    (net (code "41") (name "Net-(RN5-R3.2)") (class "Default")
      (node (ref "RN5") (pin "6") (pinfunction "R3.2_6") (pintype "unspecified"))
      (node (ref "U3") (pin "11") (pinfunction "QF_11") (pintype "unspecified"))
    )
    (net (code "42") (name "Net-(RN5-R4.2)") (class "Default")
      (node (ref "RN5") (pin "5") (pinfunction "R4.2_5") (pintype "unspecified"))
      (node (ref "U3") (pin "10") (pinfunction "QE_10") (pintype "unspecified"))
    )
    (net (code "43") (name "Net-(U1-QA)") (class "Default")
      (node (ref "RN1") (pin "5") (pinfunction "5_5") (pintype "input"))
      (node (ref "U1") (pin "3") (pinfunction "QA_3") (pintype "unspecified"))
    )
    (net (code "44") (name "Net-(U1-QB)") (class "Default")
      (node (ref "RN1") (pin "6") (pinfunction "6_6") (pintype "input"))
      (node (ref "U1") (pin "4") (pinfunction "QB_4") (pintype "unspecified"))
    )
    (net (code "45") (name "Net-(U1-QC)") (class "Default")
      (node (ref "RN1") (pin "7") (pinfunction "7_7") (pintype "input"))
      (node (ref "U1") (pin "5") (pinfunction "QC_5") (pintype "unspecified"))
    )
    (net (code "46") (name "Net-(U1-QD)") (class "Default")
      (node (ref "RN1") (pin "8") (pinfunction "8_8") (pintype "input"))
      (node (ref "U1") (pin "6") (pinfunction "QD_6") (pintype "unspecified"))
    )
    (net (code "47") (name "Net-(U1-QE)") (class "Default")
      (node (ref "RN2") (pin "5") (pinfunction "5_5") (pintype "input"))
      (node (ref "U1") (pin "10") (pinfunction "QE_10") (pintype "unspecified"))
    )
    (net (code "48") (name "Net-(U1-QF)") (class "Default")
      (node (ref "RN2") (pin "6") (pinfunction "6_6") (pintype "input"))
      (node (ref "U1") (pin "11") (pinfunction "QF_11") (pintype "unspecified"))
    )
    (net (code "49") (name "Net-(U1-QG)") (class "Default")
      (node (ref "RN2") (pin "7") (pinfunction "7_7") (pintype "input"))
      (node (ref "U1") (pin "12") (pinfunction "QG_12") (pintype "unspecified"))
    )
    (net (code "50") (name "Net-(U5-QA)") (class "Default")
      (node (ref "RN6") (pin "5") (pinfunction "5_5") (pintype "input"))
      (node (ref "U5") (pin "3") (pinfunction "QA_3") (pintype "unspecified"))
    )
    (net (code "51") (name "Net-(U5-QB)") (class "Default")
      (node (ref "RN6") (pin "6") (pinfunction "6_6") (pintype "input"))
      (node (ref "U5") (pin "4") (pinfunction "QB_4") (pintype "unspecified"))
    )
    (net (code "52") (name "Net-(U5-QC)") (class "Default")
      (node (ref "RN6") (pin "7") (pinfunction "7_7") (pintype "input"))
      (node (ref "U5") (pin "5") (pinfunction "QC_5") (pintype "unspecified"))
    )
    (net (code "53") (name "Net-(U5-QD)") (class "Default")
      (node (ref "RN6") (pin "8") (pinfunction "8_8") (pintype "input"))
      (node (ref "U5") (pin "6") (pinfunction "QD_6") (pintype "unspecified"))
    )
    (net (code "54") (name "Net-(U5-QE)") (class "Default")
      (node (ref "RN7") (pin "5") (pinfunction "5_5") (pintype "input"))
      (node (ref "U5") (pin "10") (pinfunction "QE_10") (pintype "unspecified"))
    )
    (net (code "55") (name "Net-(U5-QF)") (class "Default")
      (node (ref "RN7") (pin "6") (pinfunction "6_6") (pintype "input"))
      (node (ref "U5") (pin "11") (pinfunction "QF_11") (pintype "unspecified"))
    )
    (net (code "56") (name "Net-(U5-QG)") (class "Default")
      (node (ref "RN7") (pin "7") (pinfunction "7_7") (pintype "input"))
      (node (ref "U5") (pin "12") (pinfunction "QG_12") (pintype "unspecified"))
    )
    (net (code "57") (name "Net-(U8-CB)") (class "Default")
      (node (ref "C14") (pin "2") (pinfunction "2_2") (pintype "input"))
      (node (ref "U8") (pin "1") (pinfunction "CB_1") (pintype "unspecified"))
    )
    (net (code "58") (name "R0") (class "Default")
      (node (ref "LED1") (pin "1") (pinfunction "-_1") (pintype "unspecified"))
      (node (ref "LED9") (pin "1") (pinfunction "-_1") (pintype "unspecified"))
      (node (ref "RN1") (pin "4") (pinfunction "4_4") (pintype "input"))
    )
    (net (code "59") (name "R1") (class "Default")
      (node (ref "LED10") (pin "1") (pinfunction "-_1") (pintype "unspecified"))
      (node (ref "LED2") (pin "1") (pinfunction "-_1") (pintype "unspecified"))
      (node (ref "RN1") (pin "3") (pinfunction "3_3") (pintype "input"))
    )
    (net (code "60") (name "R2") (class "Default")
      (node (ref "LED11") (pin "1") (pinfunction "-_1") (pintype "unspecified"))
      (node (ref "LED3") (pin "1") (pinfunction "-_1") (pintype "unspecified"))
      (node (ref "RN1") (pin "2") (pinfunction "2_2") (pintype "input"))
    )
    (net (code "61") (name "R3") (class "Default")
      (node (ref "LED12") (pin "1") (pinfunction "-_1") (pintype "unspecified"))
      (node (ref "LED4") (pin "1") (pinfunction "-_1") (pintype "unspecified"))
      (node (ref "RN1") (pin "1") (pinfunction "1_1") (pintype "input"))
    )
    (net (code "62") (name "R4") (class "Default")
      (node (ref "LED13") (pin "1") (pinfunction "-_1") (pintype "unspecified"))
      (node (ref "LED5") (pin "1") (pinfunction "-_1") (pintype "unspecified"))
      (node (ref "RN2") (pin "4") (pinfunction "4_4") (pintype "input"))
    )
    (net (code "63") (name "R5") (class "Default")
      (node (ref "LED14") (pin "1") (pinfunction "-_1") (pintype "unspecified"))
      (node (ref "LED6") (pin "1") (pinfunction "-_1") (pintype "unspecified"))
      (node (ref "RN2") (pin "3") (pinfunction "3_3") (pintype "input"))
    )
    (net (code "64") (name "R6") (class "Default")
      (node (ref "LED15") (pin "1") (pinfunction "-_1") (pintype "unspecified"))
      (node (ref "LED7") (pin "1") (pinfunction "-_1") (pintype "unspecified"))
      (node (ref "RN2") (pin "2") (pinfunction "2_2") (pintype "input"))
    )
    (net (code "65") (name "R7") (class "Default")
      (node (ref "LED16") (pin "1") (pinfunction "-_1") (pintype "unspecified"))
      (node (ref "LED8") (pin "1") (pinfunction "-_1") (pintype "unspecified"))
      (node (ref "RN2") (pin "1") (pinfunction "1_1") (pintype "input"))
    )
    (net (code "66") (name "RDIS") (class "Default")
      (node (ref "R1") (pin "3") (pinfunction "3_3") (pintype "unspecified"))
      (node (ref "RN3") (pin "4") (pinfunction "4_4") (pintype "input"))
      (node (ref "U2") (pin "7") (pinfunction "DISCH_7") (pintype "unspecified"))
    )
    (net (code "67") (name "RIN") (class "Default")
      (node (ref "J3") (pin "2") (pinfunction "2_2") (pintype "input"))
      (node (ref "U7") (pin "1") (pinfunction "1A_1") (pintype "unspecified"))
    )
    (net (code "68") (name "RQ") (class "Default")
      (node (ref "J3") (pin "1") (pinfunction "1_1") (pintype "input"))
      (node (ref "RN2") (pin "8") (pinfunction "8_8") (pintype "input"))
      (node (ref "U1") (pin "13") (pinfunction "QH_13") (pintype "unspecified"))
    )
    (net (code "69") (name "RTT") (class "Default")
      (node (ref "C4") (pin "1") (pinfunction "1_1") (pintype "input"))
      (node (ref "RN3") (pin "5") (pinfunction "5_5") (pintype "input"))
      (node (ref "U2") (pin "2") (pinfunction "TRIG#_2") (pintype "unspecified"))
      (node (ref "U2") (pin "6") (pinfunction "THRES_6") (pintype "unspecified"))
    )
    (net (code "70") (name "R_CLOCK") (class "Default")
      (node (ref "J1") (pin "3") (pinfunction "3_3") (pintype "input"))
      (node (ref "J2") (pin "3") (pinfunction "3_3") (pintype "input"))
      (node (ref "U1") (pin "8") (pinfunction "CLOCK_8") (pintype "unspecified"))
      (node (ref "U2") (pin "3") (pinfunction "OUT_3") (pintype "unspecified"))
    )
    (net (code "71") (name "unconnected-(DC1-Pad3)") (class "Default")
      (node (ref "DC1") (pin "3") (pinfunction "3_3") (pintype "unspecified+no_connect"))
    )
    (net (code "72") (name "unconnected-(R1-Pad1)") (class "Default")
      (node (ref "R1") (pin "1") (pinfunction "1_1") (pintype "unspecified+no_connect"))
    )
    (net (code "73") (name "unconnected-(R2-Pad1)") (class "Default")
      (node (ref "R2") (pin "1") (pinfunction "1_1") (pintype "unspecified+no_connect"))
    )
    (net (code "74") (name "unconnected-(R3-Pad1)") (class "Default")
      (node (ref "R3") (pin "1") (pinfunction "1_1") (pintype "unspecified+no_connect"))
    )
    (net (code "75") (name "unconnected-(R6-Pad1)") (class "Default")
      (node (ref "R6") (pin "1") (pinfunction "1_1") (pintype "unspecified+no_connect"))
    )
    (net (code "76") (name "unconnected-(R7-Pad1)") (class "Default")
      (node (ref "R7") (pin "1") (pinfunction "1_1") (pintype "unspecified+no_connect"))
    )
    (net (code "77") (name "unconnected-(RN3-Pad1)") (class "Default")
      (node (ref "RN3") (pin "1") (pinfunction "1_1") (pintype "input+no_connect"))
    )
    (net (code "78") (name "unconnected-(RN3-Pad8)") (class "Default")
      (node (ref "RN3") (pin "8") (pinfunction "8_8") (pintype "input+no_connect"))
    )
    (net (code "79") (name "unconnected-(U2-CONT-Pad5)") (class "Default")
      (node (ref "U2") (pin "5") (pinfunction "CONT_5") (pintype "unspecified+no_connect"))
    )
    (net (code "80") (name "unconnected-(U4-CONT-Pad5)") (class "Default")
      (node (ref "U4") (pin "5") (pinfunction "CONT_5") (pintype "unspecified+no_connect"))
    )
    (net (code "81") (name "unconnected-(U6-CONT-Pad5)") (class "Default")
      (node (ref "U6") (pin "5") (pinfunction "CONT_5") (pintype "unspecified+no_connect"))
    )
    (net (code "82") (name "unconnected-(U8-NC-Pad2)") (class "Default")
      (node (ref "U8") (pin "2") (pinfunction "NC_2") (pintype "unspecified+no_connect"))
    )
    (net (code "83") (name "unconnected-(U8-NC-Pad3)") (class "Default")
      (node (ref "U8") (pin "3") (pinfunction "NC_3") (pintype "unspecified+no_connect"))
    )
    (net (code "84") (name "~BQ") (class "Default")
      (node (ref "J3") (pin "3") (pinfunction "3_3") (pintype "input"))
      (node (ref "U5") (pin "1") (pinfunction "A_1") (pintype "unspecified"))
      (node (ref "U5") (pin "2") (pinfunction "B_2") (pintype "unspecified"))
      (node (ref "U7") (pin "2") (pinfunction "3Y_2") (pintype "unspecified"))
    )
    (net (code "85") (name "~GQ") (class "Default")
      (node (ref "J5") (pin "3") (pinfunction "3_3") (pintype "input"))
      (node (ref "U3") (pin "1") (pinfunction "A_1") (pintype "unspecified"))
      (node (ref "U3") (pin "2") (pinfunction "B_2") (pintype "unspecified"))
      (node (ref "U7") (pin "5") (pinfunction "2Y_5") (pintype "unspecified"))
    )
    (net (code "86") (name "~RQ") (class "Default")
      (node (ref "J4") (pin "3") (pinfunction "3_3") (pintype "input"))
      (node (ref "U1") (pin "1") (pinfunction "A_1") (pintype "unspecified"))
      (node (ref "U1") (pin "2") (pinfunction "B_2") (pintype "unspecified"))
      (node (ref "U7") (pin "7") (pinfunction "1Y_7") (pintype "unspecified"))
    )
  )
)
